# CH32L103C8T6-R0.net
KiCad netlist of a schematic drawn in Altium Designer
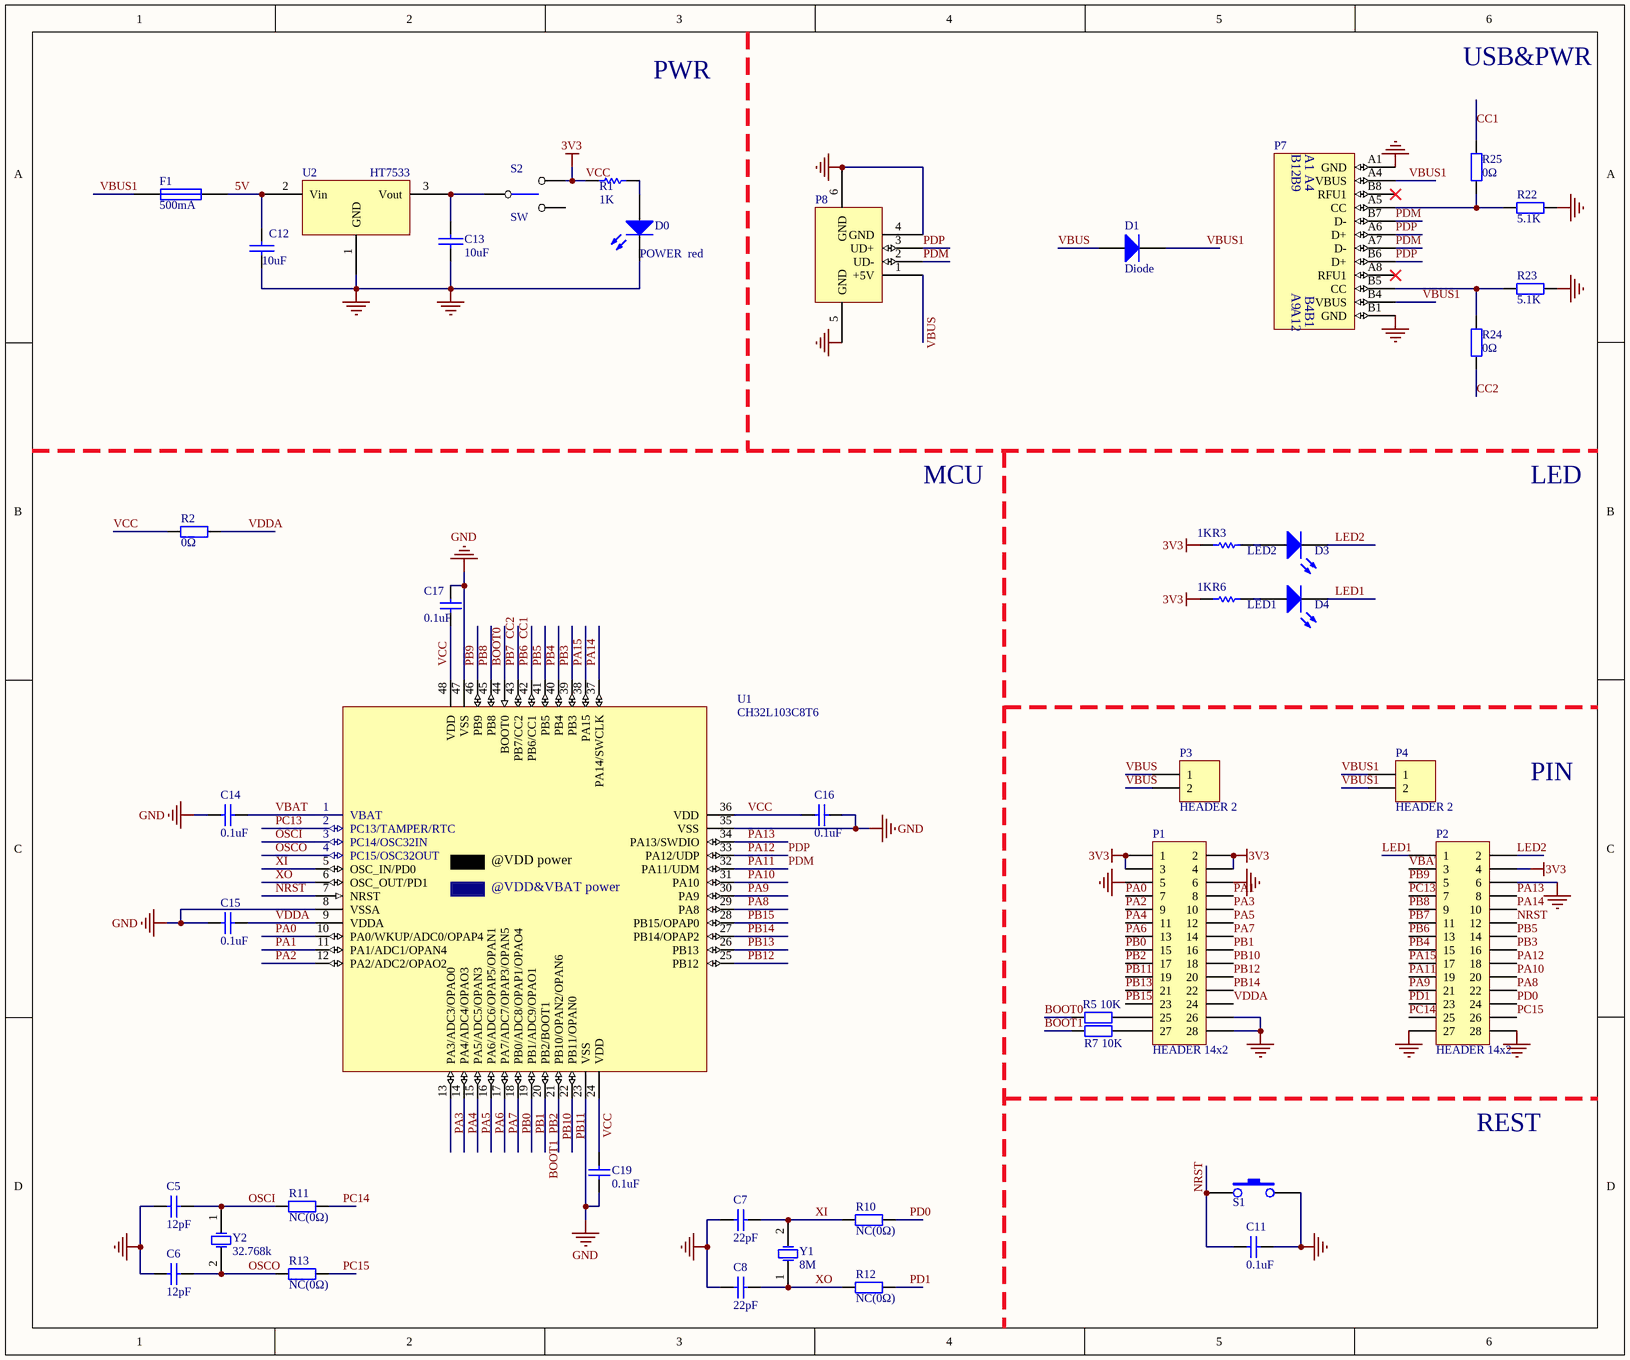
[diagram p0: CH32L103C8T6-R0.SchDoc]

(export (version "E")
  (design (tool "Eeschema 10.0.6"))
  (components
    (comp (ref "C5")
      (value "12pF")
      (footprint "0603_C")
      (description "Capacitor")
      (fields (field (name "PUBLISHER") "Altium Limited"))
      (libsource (lib "*") (part "Cap"))
    )
    (comp (ref "C6")
      (value "12pF")
      (footprint "0603_C")
      (description "Capacitor")
      (fields (field (name "PUBLISHER") "Altium Limited"))
      (libsource (lib "*") (part "Cap"))
    )
    (comp (ref "C7")
      (value "22pF")
      (footprint "0603_C")
      (description "Capacitor")
      (fields (field (name "PUBLISHER") "Altium Limited"))
      (libsource (lib "*") (part "Cap"))
    )
    (comp (ref "C8")
      (value "22pF")
      (footprint "0603_C")
      (description "Capacitor")
      (fields (field (name "PUBLISHER") "Altium Limited"))
      (libsource (lib "*") (part "Cap"))
    )
    (comp (ref "C11")
      (value "0.1uF")
      (footprint "0603_C")
      (description "Capacitor")
      (fields (field (name "PUBLISHER") "Altium Limited"))
      (libsource (lib "*") (part "Cap"))
    )
    (comp (ref "C12")
      (value "10uF")
      (footprint "0603_C")
      (description "Capacitor")
      (libsource (lib "*") (part "CAP"))
    )
    (comp (ref "C13")
      (value "10uF")
      (footprint "0603_C")
      (description "Capacitor")
      (libsource (lib "*") (part "CAP"))
    )
    (comp (ref "C14")
      (value "0.1uF")
      (footprint "0603_C")
      (description "Capacitor")
      (fields (field (name "PUBLISHER") "Altium Limited"))
      (libsource (lib "*") (part "Cap"))
    )
    (comp (ref "C15")
      (value "0.1uF")
      (footprint "0603_C")
      (description "Capacitor")
      (fields (field (name "PUBLISHER") "Altium Limited"))
      (libsource (lib "*") (part "Cap"))
    )
    (comp (ref "C16")
      (value "0.1uF")
      (footprint "0603_C")
      (description "Capacitor")
      (fields (field (name "PUBLISHER") "Altium Limited"))
      (libsource (lib "*") (part "Cap"))
    )
    (comp (ref "C17")
      (value "0.1uF")
      (footprint "0603_C")
      (description "Capacitor")
      (fields (field (name "PUBLISHER") "Altium Limited"))
      (libsource (lib "*") (part "Cap"))
    )
    (comp (ref "C19")
      (value "0.1uF")
      (footprint "0603_C")
      (description "Capacitor")
      (fields (field (name "PUBLISHER") "Altium Limited"))
      (libsource (lib "*") (part "Cap"))
    )
    (comp (ref "D0")
      (value "POWER  red")
      (footprint "0603+")
      (description "Typical INFRARED GaAs LED")
      (fields (field (name "PUBLISHER") "Altium Limited"))
      (libsource (lib "*") (part "LED0"))
    )
    (comp (ref "D1")
      (value "Diode")
      (footprint "SOD-123")
      (description "Default Diode")
      (fields (field (name "PUBLISHER") "Altium Limited"))
      (libsource (lib "Miscellaneous Devices") (part "Diode"))
    )
    (comp (ref "D3")
      (value "LED2")
      (footprint "0603+")
      (description "Typical INFRARED GaAs LED")
      (fields (field (name "PUBLISHER") "Altium Limited"))
      (libsource (lib "*") (part "LED0"))
    )
    (comp (ref "D4")
      (value "LED1")
      (footprint "0603+")
      (description "Typical INFRARED GaAs LED")
      (fields (field (name "PUBLISHER") "Altium Limited"))
      (libsource (lib "*") (part "LED0"))
    )
    (comp (ref "F1")
      (value "500mA")
      (footprint "0603")
      (description "Fuse")
      (libsource (lib "*") (part "FUSE1"))
    )
    (comp (ref "P1")
      (value "HEADER 14x2")
      (footprint "MYPCB:IDC28-2.54MM")
      (description "Header, 14-Pin, Dual row")
      (libsource (lib "wch_sch_others") (part "HEADER 14x2"))
    )
    (comp (ref "P2")
      (value "HEADER 14x2")
      (footprint "MYPCB:IDC28-2.54MM")
      (description "Header, 14-Pin, Dual row")
      (libsource (lib "wch_sch_others") (part "HEADER 14x2"))
    )
    (comp (ref "P3")
      (value "HEADER 2")
      (footprint "SIP2-2.54mm")
      (description "Header, 2-Pin")
      (libsource (lib "wch_sch_others") (part "HEADER 2"))
    )
    (comp (ref "P4")
      (value "HEADER 2")
      (footprint "SIP2-2.54mm")
      (description "Header, 2-Pin")
      (libsource (lib "wch_sch_others") (part "HEADER 2"))
    )
    (comp (ref "P7")
      (value "TYPE-C")
      (footprint "TYPE-C-Receptacle-2.0")
      (libsource (lib "*") (part "TYPE-C1"))
    )
    (comp (ref "P8")
      (value "USB_A")
      (footprint "USBAF")
      (description "USB Port")
      (libsource (lib "*") (part "USB"))
    )
    (comp (ref "R1")
      (value "1K")
      (footprint "0603")
      (description "Semiconductor Resistor")
      (libsource (lib "*") (part "Res Semi"))
    )
    (comp (ref "R2")
      (value "0Ω")
      (footprint "0603")
      (description "Resistor")
      (libsource (lib "") (part "Res2_2"))
    )
    (comp (ref "R3")
      (value "1K")
      (footprint "0603")
      (description "Semiconductor Resistor")
      (libsource (lib "*") (part "Res Semi"))
    )
    (comp (ref "R5")
      (value "10K")
      (footprint "0603")
      (description "Resistor")
      (fields (field (name "PUBLISHER") "Altium Limited"))
      (libsource (lib "*") (part "Res2"))
    )
    (comp (ref "R6")
      (value "1K")
      (footprint "0603")
      (description "Semiconductor Resistor")
      (libsource (lib "*") (part "Res Semi"))
    )
    (comp (ref "R7")
      (value "10K")
      (footprint "0603")
      (description "Resistor")
      (fields (field (name "PUBLISHER") "Altium Limited"))
      (libsource (lib "*") (part "Res2"))
    )
    (comp (ref "R10")
      (value "NC(0Ω)")
      (footprint "0603")
      (description "Resistor")
      (libsource (lib "") (part "Res2_1"))
    )
    (comp (ref "R11")
      (value "NC(0Ω)")
      (footprint "0603")
      (description "Resistor")
      (libsource (lib "") (part "Res2_1"))
    )
    (comp (ref "R12")
      (value "NC(0Ω)")
      (footprint "0603")
      (description "Resistor")
      (libsource (lib "") (part "Res2_1"))
    )
    (comp (ref "R13")
      (value "NC(0Ω)")
      (footprint "0603")
      (description "Resistor")
      (libsource (lib "") (part "Res2_1"))
    )
    (comp (ref "R22")
      (value "5.1K")
      (footprint "0603")
      (description "Resistor")
      (libsource (lib "") (part "Res2_2"))
    )
    (comp (ref "R23")
      (value "5.1K")
      (footprint "0603")
      (description "Resistor")
      (libsource (lib "") (part "Res2_2"))
    )
    (comp (ref "R24")
      (value "0Ω")
      (footprint "0603")
      (description "Resistor")
      (libsource (lib "Miscellaneous Devices") (part "Res2"))
    )
    (comp (ref "R25")
      (value "0Ω")
      (footprint "0603")
      (description "Resistor")
      (libsource (lib "Miscellaneous Devices") (part "Res2"))
    )
    (comp (ref "S1") (value "KEY") (footprint "贴片按键") (libsource (lib "*") (part "KEY")))
    (comp (ref "S2") (value "SW") (footprint "SW1") (libsource (lib "*") (part "SW")))
    (comp (ref "U1")
      (value "CH32L103C8T6")
      (footprint "LQFP48")
      (description "RISC-V LMD-MCU, 96MHz, USB, Type-C/PD, CAN, OPA, lower power")
      (libsource (lib "CHXXX") (part "CH32L103C8T6"))
    )
    (comp (ref "U2")
      (value "HT7533")
      (footprint "SOT-89")
      (libsource (lib "wch_sch_others") (part "1117-3.3V"))
    )
    (comp (ref "Y1")
      (value "8M")
      (footprint "XT_AT49")
      (description "Crystal Oscillator")
      (fields (field (name "PUBLISHER") "Altium Limited"))
      (libsource (lib "*") (part "XTAL"))
    )
    (comp (ref "Y2")
      (value "32.768k")
      (footprint "FC-135")
      (description "Crystal Oscillator")
      (fields (field (name "PUBLISHER") "Altium Limited"))
      (libsource (lib "*") (part "XTAL"))
    )
  )
  (nets
    (net (code "1") (name "/5V") (class "Default")
      (node (ref "C12") (pin "1") (pinfunction "1_1") (pintype "passive"))
      (node (ref "F1") (pin "2") (pinfunction "2_2") (pintype "passive"))
      (node (ref "U2") (pin "2") (pinfunction "Vin_2") (pintype "passive"))
    )
    (net (code "3") (name "/BOOT0") (class "Default")
      (node (ref "R5") (pin "1") (pinfunction "1_1") (pintype "passive"))
      (node (ref "U1") (pin "44") (pinfunction "BOOT0_44") (pintype "input"))
    )
    (net (code "4") (name "/BOOT1") (class "Default")
      (node (ref "P1") (pin "17") (pinfunction "17_17") (pintype "passive"))
      (node (ref "R7") (pin "1") (pinfunction "1_1") (pintype "passive"))
      (node (ref "U1") (pin "20") (pinfunction "PB2/BOOT1_20") (pintype "bidirectional"))
    )
    (net (code "5") (name "/CC1") (class "Default")
      (node (ref "P2") (pin "13") (pinfunction "13_13") (pintype "passive"))
      (node (ref "R25") (pin "2") (pinfunction "2_2") (pintype "passive"))
      (node (ref "U1") (pin "42") (pinfunction "PB6/CC1_42") (pintype "bidirectional"))
    )
    (net (code "6") (name "/CC2") (class "Default")
      (node (ref "P2") (pin "11") (pinfunction "11_11") (pintype "passive"))
      (node (ref "R24") (pin "1") (pinfunction "1_1") (pintype "passive"))
      (node (ref "U1") (pin "43") (pinfunction "PB7/CC2_43") (pintype "bidirectional"))
    )
    (net (code "7") (name "/LED1") (class "Default")
      (node (ref "D4") (pin "2") (pinfunction "K_2") (pintype "passive"))
      (node (ref "P2") (pin "1") (pinfunction "1_1") (pintype "passive"))
    )
    (net (code "8") (name "/LED2") (class "Default")
      (node (ref "D3") (pin "2") (pinfunction "K_2") (pintype "passive"))
      (node (ref "P2") (pin "2") (pinfunction "2_2") (pintype "passive"))
    )
    (net (code "9") (name "/NRST") (class "Default")
      (node (ref "C11") (pin "2") (pinfunction "2_2") (pintype "passive"))
      (node (ref "P2") (pin "12") (pinfunction "12_12") (pintype "passive"))
      (node (ref "S1") (pin "1") (pinfunction "1_1") (pintype "passive"))
      (node (ref "U1") (pin "7") (pinfunction "NRST_7") (pintype "input"))
    )
    (net (code "10") (name "/OSCI") (class "Default")
      (node (ref "C5") (pin "1") (pinfunction "1_1") (pintype "passive"))
      (node (ref "R11") (pin "2") (pinfunction "2_2") (pintype "passive"))
      (node (ref "U1") (pin "3") (pinfunction "PC14/OSC32IN_3") (pintype "bidirectional"))
      (node (ref "Y2") (pin "1") (pinfunction "OSC1_1") (pintype "passive"))
    )
    (net (code "11") (name "/OSCO") (class "Default")
      (node (ref "C6") (pin "1") (pinfunction "1_1") (pintype "passive"))
      (node (ref "R13") (pin "2") (pinfunction "2_2") (pintype "passive"))
      (node (ref "U1") (pin "4") (pinfunction "PC15/OSC32OUT_4") (pintype "bidirectional"))
      (node (ref "Y2") (pin "2") (pinfunction "OSC2_2") (pintype "passive"))
    )
    (net (code "12") (name "/PA0") (class "Default")
      (node (ref "P1") (pin "7") (pinfunction "7_7") (pintype "passive"))
      (node (ref "U1") (pin "10") (pinfunction "PA0/WKUP/ADC0/OPAP4_10") (pintype "bidirectional"))
    )
    (net (code "13") (name "/PA1") (class "Default")
      (node (ref "P1") (pin "8") (pinfunction "8_8") (pintype "passive"))
      (node (ref "U1") (pin "11") (pinfunction "PA1/ADC1/OPAN4_11") (pintype "bidirectional"))
    )
    (net (code "14") (name "/PA2") (class "Default")
      (node (ref "P1") (pin "9") (pinfunction "9_9") (pintype "passive"))
      (node (ref "U1") (pin "12") (pinfunction "PA2/ADC2/OPAO2_12") (pintype "bidirectional"))
    )
    (net (code "15") (name "/PA3") (class "Default")
      (node (ref "P1") (pin "10") (pinfunction "10_10") (pintype "passive"))
      (node (ref "U1") (pin "13") (pinfunction "PA3/ADC3/OPAO0_13") (pintype "bidirectional"))
    )
    (net (code "16") (name "/PA4") (class "Default")
      (node (ref "P1") (pin "11") (pinfunction "11_11") (pintype "passive"))
      (node (ref "U1") (pin "14") (pinfunction "PA4/ADC4/OPAO3_14") (pintype "bidirectional"))
    )
    (net (code "17") (name "/PA5") (class "Default")
      (node (ref "P1") (pin "12") (pinfunction "12_12") (pintype "passive"))
      (node (ref "U1") (pin "15") (pinfunction "PA5/ADC5/OPAN3_15") (pintype "bidirectional"))
    )
    (net (code "18") (name "/PA6") (class "Default")
      (node (ref "P1") (pin "13") (pinfunction "13_13") (pintype "passive"))
      (node (ref "U1") (pin "16") (pinfunction "PA6/ADC6/OPAP5/OPAN1_16") (pintype "bidirectional"))
    )
    (net (code "19") (name "/PA7") (class "Default")
      (node (ref "P1") (pin "14") (pinfunction "14_14") (pintype "passive"))
      (node (ref "U1") (pin "17") (pinfunction "PA7/ADC7/OPAP3/OPAN5_17") (pintype "bidirectional"))
    )
    (net (code "20") (name "/PA8") (class "Default")
      (node (ref "P2") (pin "22") (pinfunction "22_22") (pintype "passive"))
      (node (ref "U1") (pin "29") (pinfunction "PA8_29") (pintype "bidirectional"))
    )
    (net (code "21") (name "/PA9") (class "Default")
      (node (ref "P2") (pin "21") (pinfunction "21_21") (pintype "passive"))
      (node (ref "U1") (pin "30") (pinfunction "PA9_30") (pintype "bidirectional"))
    )
    (net (code "22") (name "/PA10") (class "Default")
      (node (ref "P2") (pin "20") (pinfunction "20_20") (pintype "passive"))
      (node (ref "U1") (pin "31") (pinfunction "PA10_31") (pintype "bidirectional"))
    )
    (net (code "23") (name "/PA11") (class "Default")
      (node (ref "P2") (pin "19") (pinfunction "19_19") (pintype "passive"))
      (node (ref "P7") (pin "A7") (pinfunction "D-_A7") (pintype "bidirectional"))
      (node (ref "P7") (pin "B7") (pinfunction "D-_B7") (pintype "bidirectional"))
      (node (ref "P8") (pin "2") (pinfunction "UD-_2") (pintype "bidirectional"))
      (node (ref "U1") (pin "32") (pinfunction "PA11/UDM_32") (pintype "bidirectional"))
    )
    (net (code "24") (name "/PA12") (class "Default")
      (node (ref "P2") (pin "18") (pinfunction "18_18") (pintype "passive"))
      (node (ref "P7") (pin "A6") (pinfunction "D+_A6") (pintype "bidirectional"))
      (node (ref "P7") (pin "B6") (pinfunction "D+_B6") (pintype "bidirectional"))
      (node (ref "P8") (pin "3") (pinfunction "UD+_3") (pintype "bidirectional"))
      (node (ref "U1") (pin "33") (pinfunction "PA12/UDP_33") (pintype "bidirectional"))
    )
    (net (code "25") (name "/PA13") (class "Default")
      (node (ref "P2") (pin "8") (pinfunction "8_8") (pintype "passive"))
      (node (ref "U1") (pin "34") (pinfunction "PA13/SWDIO_34") (pintype "bidirectional"))
    )
    (net (code "26") (name "/PA14") (class "Default")
      (node (ref "P2") (pin "10") (pinfunction "10_10") (pintype "passive"))
      (node (ref "U1") (pin "37") (pinfunction "PA14/SWCLK_37") (pintype "bidirectional"))
    )
    (net (code "27") (name "/PA15") (class "Default")
      (node (ref "P2") (pin "17") (pinfunction "17_17") (pintype "passive"))
      (node (ref "U1") (pin "38") (pinfunction "PA15_38") (pintype "bidirectional"))
    )
    (net (code "28") (name "/PB0") (class "Default")
      (node (ref "P1") (pin "15") (pinfunction "15_15") (pintype "passive"))
      (node (ref "U1") (pin "18") (pinfunction "PB0/ADC8/OPAP1/OPAO4_18") (pintype "bidirectional"))
    )
    (net (code "29") (name "/PB1") (class "Default")
      (node (ref "P1") (pin "16") (pinfunction "16_16") (pintype "passive"))
      (node (ref "U1") (pin "19") (pinfunction "PB1/ADC9/OPAO1_19") (pintype "bidirectional"))
    )
    (net (code "30") (name "/PB3") (class "Default")
      (node (ref "P2") (pin "16") (pinfunction "16_16") (pintype "passive"))
      (node (ref "U1") (pin "39") (pinfunction "PB3_39") (pintype "bidirectional"))
    )
    (net (code "31") (name "/PB4") (class "Default")
      (node (ref "P2") (pin "15") (pinfunction "15_15") (pintype "passive"))
      (node (ref "U1") (pin "40") (pinfunction "PB4_40") (pintype "bidirectional"))
    )
    (net (code "32") (name "/PB5") (class "Default")
      (node (ref "P2") (pin "14") (pinfunction "14_14") (pintype "passive"))
      (node (ref "U1") (pin "41") (pinfunction "PB5_41") (pintype "bidirectional"))
    )
    (net (code "33") (name "/PB8") (class "Default")
      (node (ref "P2") (pin "9") (pinfunction "9_9") (pintype "passive"))
      (node (ref "U1") (pin "45") (pinfunction "PB8_45") (pintype "bidirectional"))
    )
    (net (code "34") (name "/PB9") (class "Default")
      (node (ref "P2") (pin "5") (pinfunction "5_5") (pintype "passive"))
      (node (ref "U1") (pin "46") (pinfunction "PB9_46") (pintype "bidirectional"))
    )
    (net (code "35") (name "/PB10") (class "Default")
      (node (ref "P1") (pin "18") (pinfunction "18_18") (pintype "passive"))
      (node (ref "U1") (pin "21") (pinfunction "PB10/OPAN2/OPAN6_21") (pintype "bidirectional"))
    )
    (net (code "36") (name "/PB11") (class "Default")
      (node (ref "P1") (pin "19") (pinfunction "19_19") (pintype "passive"))
      (node (ref "U1") (pin "22") (pinfunction "PB11/OPAN0_22") (pintype "bidirectional"))
    )
    (net (code "37") (name "/PB12") (class "Default")
      (node (ref "P1") (pin "20") (pinfunction "20_20") (pintype "passive"))
      (node (ref "U1") (pin "25") (pinfunction "PB12_25") (pintype "bidirectional"))
    )
    (net (code "38") (name "/PB13") (class "Default")
      (node (ref "P1") (pin "21") (pinfunction "21_21") (pintype "passive"))
      (node (ref "U1") (pin "26") (pinfunction "PB13_26") (pintype "bidirectional"))
    )
    (net (code "39") (name "/PB14") (class "Default")
      (node (ref "P1") (pin "22") (pinfunction "22_22") (pintype "passive"))
      (node (ref "U1") (pin "27") (pinfunction "PB14/OPAP2_27") (pintype "bidirectional"))
    )
    (net (code "40") (name "/PB15") (class "Default")
      (node (ref "P1") (pin "23") (pinfunction "23_23") (pintype "passive"))
      (node (ref "U1") (pin "28") (pinfunction "PB15/OPAP0_28") (pintype "bidirectional"))
    )
    (net (code "41") (name "/PC13") (class "Default")
      (node (ref "P2") (pin "7") (pinfunction "7_7") (pintype "passive"))
      (node (ref "U1") (pin "2") (pinfunction "PC13/TAMPER/RTC_2") (pintype "bidirectional"))
    )
    (net (code "42") (name "/PC14") (class "Default")
      (node (ref "P2") (pin "25") (pinfunction "25_25") (pintype "passive"))
      (node (ref "R11") (pin "1") (pinfunction "1_1") (pintype "passive"))
    )
    (net (code "43") (name "/PC15") (class "Default")
      (node (ref "P2") (pin "26") (pinfunction "26_26") (pintype "passive"))
      (node (ref "R13") (pin "1") (pinfunction "1_1") (pintype "passive"))
    )
    (net (code "44") (name "/PD0") (class "Default")
      (node (ref "P2") (pin "24") (pinfunction "24_24") (pintype "passive"))
      (node (ref "R10") (pin "1") (pinfunction "1_1") (pintype "passive"))
    )
    (net (code "45") (name "/PD1") (class "Default")
      (node (ref "P2") (pin "23") (pinfunction "23_23") (pintype "passive"))
      (node (ref "R12") (pin "1") (pinfunction "1_1") (pintype "passive"))
    )
    (net (code "46") (name "/VBAT") (class "Default")
      (node (ref "C14") (pin "1") (pinfunction "1_1") (pintype "passive"))
      (node (ref "P2") (pin "3") (pinfunction "3_3") (pintype "passive"))
      (node (ref "U1") (pin "1") (pinfunction "VBAT_1") (pintype "power_in"))
    )
    (net (code "47") (name "/VBUS") (class "Default")
      (node (ref "D1") (pin "1") (pinfunction "A_1") (pintype "passive"))
      (node (ref "P3") (pin "1") (pinfunction "1_1") (pintype "passive"))
      (node (ref "P3") (pin "2") (pinfunction "2_2") (pintype "passive"))
      (node (ref "P8") (pin "1") (pinfunction "+5V_1") (pintype "power_in"))
    )
    (net (code "48") (name "/VBUS1") (class "Default")
      (node (ref "D1") (pin "2") (pinfunction "K_2") (pintype "passive"))
      (node (ref "F1") (pin "1") (pinfunction "1_1") (pintype "passive"))
      (node (ref "P4") (pin "1") (pinfunction "1_1") (pintype "passive"))
      (node (ref "P4") (pin "2") (pinfunction "2_2") (pintype "passive"))
      (node (ref "P7") (pin "A4") (pinfunction "VBUS_A4") (pintype "bidirectional"))
      (node (ref "P7") (pin "B4") (pinfunction "VBUS_B4") (pintype "bidirectional"))
    )
    (net (code "49") (name "/VDDA") (class "Default")
      (node (ref "C15") (pin "1") (pinfunction "1_1") (pintype "passive"))
      (node (ref "P1") (pin "24") (pinfunction "24_24") (pintype "passive"))
      (node (ref "R2") (pin "2") (pinfunction "2_2") (pintype "passive"))
      (node (ref "U1") (pin "9") (pinfunction "VDDA_9") (pintype "power_in"))
    )
    (net (code "50") (name "/XI") (class "Default")
      (node (ref "C7") (pin "2") (pinfunction "2_2") (pintype "passive"))
      (node (ref "R10") (pin "2") (pinfunction "2_2") (pintype "passive"))
      (node (ref "U1") (pin "5") (pinfunction "OSC_IN/PD0_5") (pintype "bidirectional"))
      (node (ref "Y1") (pin "2") (pinfunction "OSC2_2") (pintype "passive"))
    )
    (net (code "51") (name "/XO") (class "Default")
      (node (ref "C8") (pin "2") (pinfunction "2_2") (pintype "passive"))
      (node (ref "R12") (pin "2") (pinfunction "2_2") (pintype "passive"))
      (node (ref "U1") (pin "6") (pinfunction "OSC_OUT/PD1_6") (pintype "bidirectional"))
      (node (ref "Y1") (pin "1") (pinfunction "OSC1_1") (pintype "passive"))
    )
    (net (code "52") (name "3V3") (class "Default")
      (node (ref "C16") (pin "1") (pinfunction "1_1") (pintype "passive"))
      (node (ref "C17") (pin "2") (pinfunction "2_2") (pintype "passive"))
      (node (ref "C19") (pin "2") (pinfunction "2_2") (pintype "passive"))
      (node (ref "P1") (pin "1") (pinfunction "1_1") (pintype "passive"))
      (node (ref "P1") (pin "2") (pinfunction "2_2") (pintype "passive"))
      (node (ref "P1") (pin "3") (pinfunction "3_3") (pintype "passive"))
      (node (ref "P1") (pin "4") (pinfunction "4_4") (pintype "passive"))
      (node (ref "P2") (pin "4") (pinfunction "4_4") (pintype "passive"))
      (node (ref "R1") (pin "2") (pinfunction "2_2") (pintype "passive"))
      (node (ref "R2") (pin "1") (pinfunction "1_1") (pintype "passive"))
      (node (ref "R3") (pin "1") (pinfunction "1_1") (pintype "passive"))
      (node (ref "R6") (pin "1") (pinfunction "1_1") (pintype "passive"))
      (node (ref "S2") (pin "3") (pinfunction "3_3") (pintype "passive"))
      (node (ref "U1") (pin "24") (pinfunction "VDD_24") (pintype "power_in"))
      (node (ref "U1") (pin "36") (pinfunction "VDD_36") (pintype "power_in"))
      (node (ref "U1") (pin "48") (pinfunction "VDD_48") (pintype "power_in"))
    )
    (net (code "53") (name "GND") (class "Default")
      (node (ref "C11") (pin "1") (pinfunction "1_1") (pintype "passive"))
      (node (ref "C12") (pin "2") (pinfunction "2_2") (pintype "passive"))
      (node (ref "C13") (pin "2") (pinfunction "2_2") (pintype "passive"))
      (node (ref "C14") (pin "2") (pinfunction "2_2") (pintype "passive"))
      (node (ref "C15") (pin "2") (pinfunction "2_2") (pintype "passive"))
      (node (ref "C16") (pin "2") (pinfunction "2_2") (pintype "passive"))
      (node (ref "C17") (pin "1") (pinfunction "1_1") (pintype "passive"))
      (node (ref "C19") (pin "1") (pinfunction "1_1") (pintype "passive"))
      (node (ref "C5") (pin "2") (pinfunction "2_2") (pintype "passive"))
      (node (ref "C6") (pin "2") (pinfunction "2_2") (pintype "passive"))
      (node (ref "C7") (pin "1") (pinfunction "1_1") (pintype "passive"))
      (node (ref "C8") (pin "1") (pinfunction "1_1") (pintype "passive"))
      (node (ref "D0") (pin "2") (pinfunction "K_2") (pintype "passive"))
      (node (ref "P1") (pin "26") (pinfunction "26_26") (pintype "passive"))
      (node (ref "P1") (pin "28") (pinfunction "28_28") (pintype "passive"))
      (node (ref "P1") (pin "5") (pinfunction "5_5") (pintype "passive"))
      (node (ref "P1") (pin "6") (pinfunction "6_6") (pintype "passive"))
      (node (ref "P2") (pin "27") (pinfunction "27_27") (pintype "passive"))
      (node (ref "P2") (pin "28") (pinfunction "28_28") (pintype "passive"))
      (node (ref "P2") (pin "6") (pinfunction "6_6") (pintype "passive"))
      (node (ref "P7") (pin "A1") (pinfunction "GND_A1") (pintype "bidirectional"))
      (node (ref "P7") (pin "B1") (pinfunction "GND_B1") (pintype "bidirectional"))
      (node (ref "P8") (pin "4") (pinfunction "GND_4") (pintype "power_in"))
      (node (ref "P8") (pin "5") (pinfunction "GND_5") (pintype "power_in"))
      (node (ref "P8") (pin "6") (pinfunction "GND_6") (pintype "power_in"))
      (node (ref "R22") (pin "2") (pinfunction "2_2") (pintype "passive"))
      (node (ref "R23") (pin "2") (pinfunction "2_2") (pintype "passive"))
      (node (ref "S1") (pin "2") (pinfunction "2_2") (pintype "passive"))
      (node (ref "U1") (pin "23") (pinfunction "VSS_23") (pintype "power_in"))
      (node (ref "U1") (pin "35") (pinfunction "VSS_35") (pintype "power_in"))
      (node (ref "U1") (pin "47") (pinfunction "VSS_47") (pintype "power_in"))
      (node (ref "U1") (pin "8") (pinfunction "VSSA_8") (pintype "power_in"))
      (node (ref "U2") (pin "1") (pinfunction "GND_1") (pintype "passive"))
    )
    (net (code "54") (name "Net-(D0-A)") (class "Default")
      (node (ref "D0") (pin "1") (pinfunction "A_1") (pintype "passive"))
      (node (ref "R1") (pin "1") (pinfunction "1_1") (pintype "passive"))
    )
    (net (code "55") (name "Net-(D3-A)") (class "Default")
      (node (ref "D3") (pin "1") (pinfunction "A_1") (pintype "passive"))
      (node (ref "R3") (pin "2") (pinfunction "2_2") (pintype "passive"))
    )
    (net (code "56") (name "Net-(D4-A)") (class "Default")
      (node (ref "D4") (pin "1") (pinfunction "A_1") (pintype "passive"))
      (node (ref "R6") (pin "2") (pinfunction "2_2") (pintype "passive"))
    )
    (net (code "57") (name "Net-(P1-Pad25)") (class "Default")
      (node (ref "P1") (pin "25") (pinfunction "25_25") (pintype "passive"))
      (node (ref "R5") (pin "2") (pinfunction "2_2") (pintype "passive"))
    )
    (net (code "58") (name "Net-(P1-Pad27)") (class "Default")
      (node (ref "P1") (pin "27") (pinfunction "27_27") (pintype "passive"))
      (node (ref "R7") (pin "2") (pinfunction "2_2") (pintype "passive"))
    )
    (net (code "59") (name "Net-(P7-CC-PadA5)") (class "Default")
      (node (ref "P7") (pin "A5") (pinfunction "CC_A5") (pintype "bidirectional"))
      (node (ref "R22") (pin "1") (pinfunction "1_1") (pintype "passive"))
      (node (ref "R25") (pin "1") (pinfunction "1_1") (pintype "passive"))
    )
    (net (code "60") (name "Net-(P7-CC-PadB5)") (class "Default")
      (node (ref "P7") (pin "B5") (pinfunction "CC_B5") (pintype "bidirectional"))
      (node (ref "R23") (pin "1") (pinfunction "1_1") (pintype "passive"))
      (node (ref "R24") (pin "2") (pinfunction "2_2") (pintype "passive"))
    )
    (net (code "61") (name "Net-(U2-Vout)") (class "Default")
      (node (ref "C13") (pin "1") (pinfunction "1_1") (pintype "passive"))
      (node (ref "S2") (pin "1") (pinfunction "1_1") (pintype "passive"))
      (node (ref "U2") (pin "3") (pinfunction "Vout_3") (pintype "passive"))
    )
    (net (code "62") (name "unconnected-(P7-RFU1-PadA8)") (class "Default")
      (node (ref "P7") (pin "A8") (pinfunction "RFU1_A8") (pintype "bidirectional+no_connect"))
    )
    (net (code "63") (name "unconnected-(P7-RFU1-PadB8)") (class "Default")
      (node (ref "P7") (pin "B8") (pinfunction "RFU1_B8") (pintype "bidirectional+no_connect"))
    )
    (net (code "64") (name "unconnected-(S2-Pad2)") (class "Default")
      (node (ref "S2") (pin "2") (pinfunction "2_2") (pintype "passive"))
    )
  )
)
